# CLKB_temp_sensors.net
KiCad netlist of a schematic drawn in Altium Designer
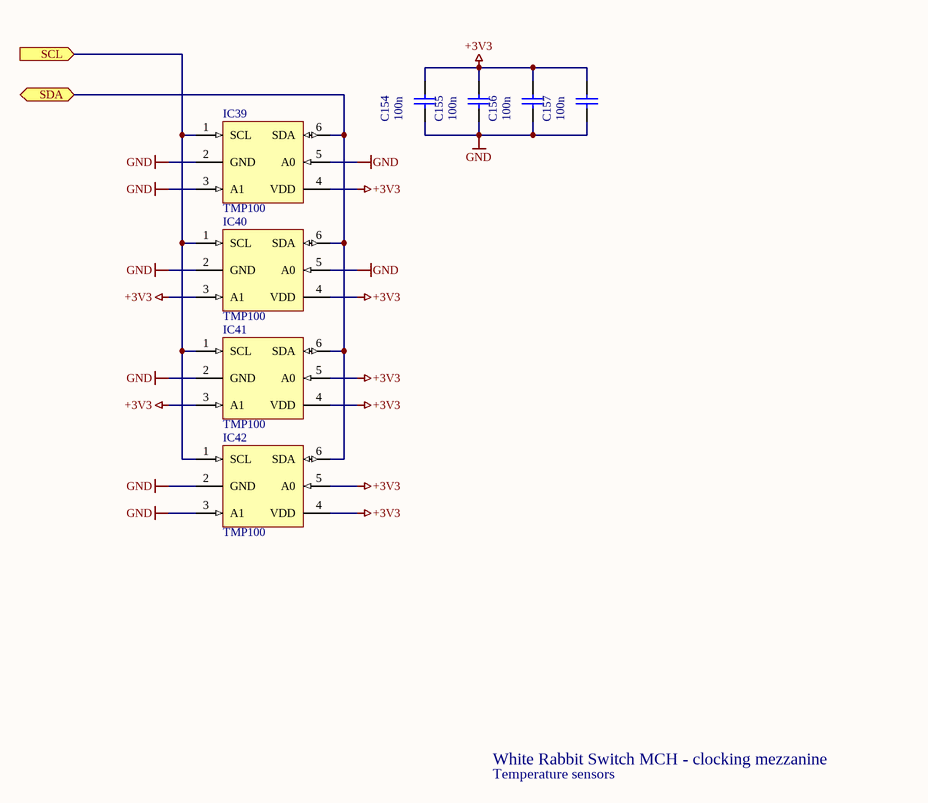
[diagram p0: CLKB_temp_sensors.SchDoc]

(export (version "E")
  (design (tool "Eeschema 10.0.6"))
  (components
    (comp (ref "C154")
      (value "100n")
      (footprint "CAPC1608X87N")
      (description "Non-polarised capacitor")
      (fields
        (field (name "PART NUMBER") "CC0603_100NF_50V_10%_X7R")
        (field (name "VOLTAGE") "50V")
        (field (name "AUTHOR") "CERN DEM JLC")
      )
      (libsource (lib "Capacitors") (part "Capacitor - non polarized"))
    )
    (comp (ref "C155")
      (value "100n")
      (footprint "CAPC1608X87N")
      (description "Non-polarised capacitor")
      (fields
        (field (name "PART NUMBER") "CC0603_100NF_50V_10%_X7R")
        (field (name "VOLTAGE") "50V")
        (field (name "AUTHOR") "CERN DEM JLC")
      )
      (libsource (lib "Capacitors") (part "Capacitor - non polarized"))
    )
    (comp (ref "C156")
      (value "100n")
      (footprint "CAPC1608X87N")
      (description "Non-polarised capacitor")
      (fields
        (field (name "PART NUMBER") "CC0603_100NF_50V_10%_X7R")
        (field (name "VOLTAGE") "50V")
        (field (name "AUTHOR") "CERN DEM JLC")
      )
      (libsource (lib "Capacitors") (part "Capacitor - non polarized"))
    )
    (comp (ref "C157")
      (value "100n")
      (footprint "CAPC1608X87N")
      (description "Non-polarised capacitor")
      (fields
        (field (name "PART NUMBER") "CC0603_100NF_50V_10%_X7R")
        (field (name "VOLTAGE") "50V")
        (field (name "AUTHOR") "CERN DEM JLC")
      )
      (libsource (lib "Capacitors") (part "Capacitor - non polarized"))
    )
    (comp (ref "IC39")
      (value "TMP100")
      (footprint "SOT23A-6L")
      (description "I2C temp. sensor")
      (libsource (lib "wr_switch") (part "TMP100"))
    )
    (comp (ref "IC40")
      (value "TMP100")
      (footprint "SOT23A-6L")
      (description "I2C temp. sensor")
      (libsource (lib "wr_switch") (part "TMP100"))
    )
    (comp (ref "IC41")
      (value "TMP100")
      (footprint "SOT23A-6L")
      (description "I2C temp. sensor")
      (libsource (lib "wr_switch") (part "TMP100"))
    )
    (comp (ref "IC42")
      (value "TMP100")
      (footprint "SOT23A-6L")
      (description "I2C temp. sensor")
      (libsource (lib "wr_switch") (part "TMP100"))
    )
  )
  (nets
    (net (code "1") (name "+3V3") (class "Default")
      (node (ref "C154") (pin "2") (pinfunction "2_2") (pintype "passive"))
      (node (ref "C155") (pin "2") (pinfunction "2_2") (pintype "passive"))
      (node (ref "C156") (pin "2") (pinfunction "2_2") (pintype "passive"))
      (node (ref "C157") (pin "2") (pinfunction "2_2") (pintype "passive"))
      (node (ref "IC39") (pin "4") (pinfunction "VDD_4") (pintype "power_in"))
      (node (ref "IC40") (pin "3") (pinfunction "A1_3") (pintype "input"))
      (node (ref "IC40") (pin "4") (pinfunction "VDD_4") (pintype "power_in"))
      (node (ref "IC41") (pin "3") (pinfunction "A1_3") (pintype "input"))
      (node (ref "IC41") (pin "4") (pinfunction "VDD_4") (pintype "power_in"))
      (node (ref "IC41") (pin "5") (pinfunction "A0_5") (pintype "input"))
      (node (ref "IC42") (pin "4") (pinfunction "VDD_4") (pintype "power_in"))
      (node (ref "IC42") (pin "5") (pinfunction "A0_5") (pintype "input"))
    )
    (net (code "2") (name "/SCL") (class "Default")
      (node (ref "IC39") (pin "1") (pinfunction "SCL_1") (pintype "input"))
      (node (ref "IC40") (pin "1") (pinfunction "SCL_1") (pintype "input"))
      (node (ref "IC41") (pin "1") (pinfunction "SCL_1") (pintype "input"))
      (node (ref "IC42") (pin "1") (pinfunction "SCL_1") (pintype "input"))
    )
    (net (code "3") (name "/SDA") (class "Default")
      (node (ref "IC39") (pin "6") (pinfunction "SDA_6") (pintype "bidirectional"))
      (node (ref "IC40") (pin "6") (pinfunction "SDA_6") (pintype "bidirectional"))
      (node (ref "IC41") (pin "6") (pinfunction "SDA_6") (pintype "bidirectional"))
      (node (ref "IC42") (pin "6") (pinfunction "SDA_6") (pintype "bidirectional"))
    )
    (net (code "4") (name "GND") (class "Default")
      (node (ref "C154") (pin "1") (pinfunction "1_1") (pintype "passive"))
      (node (ref "C155") (pin "1") (pinfunction "1_1") (pintype "passive"))
      (node (ref "C156") (pin "1") (pinfunction "1_1") (pintype "passive"))
      (node (ref "C157") (pin "1") (pinfunction "1_1") (pintype "passive"))
      (node (ref "IC39") (pin "2") (pinfunction "GND_2") (pintype "power_in"))
      (node (ref "IC39") (pin "3") (pinfunction "A1_3") (pintype "input"))
      (node (ref "IC39") (pin "5") (pinfunction "A0_5") (pintype "input"))
      (node (ref "IC40") (pin "2") (pinfunction "GND_2") (pintype "power_in"))
      (node (ref "IC40") (pin "5") (pinfunction "A0_5") (pintype "input"))
      (node (ref "IC41") (pin "2") (pinfunction "GND_2") (pintype "power_in"))
      (node (ref "IC42") (pin "2") (pinfunction "GND_2") (pintype "power_in"))
      (node (ref "IC42") (pin "3") (pinfunction "A1_3") (pintype "input"))
    )
  )
)
